# componant_example.net
KiCad netlist of a schematic drawn in Altium Designer
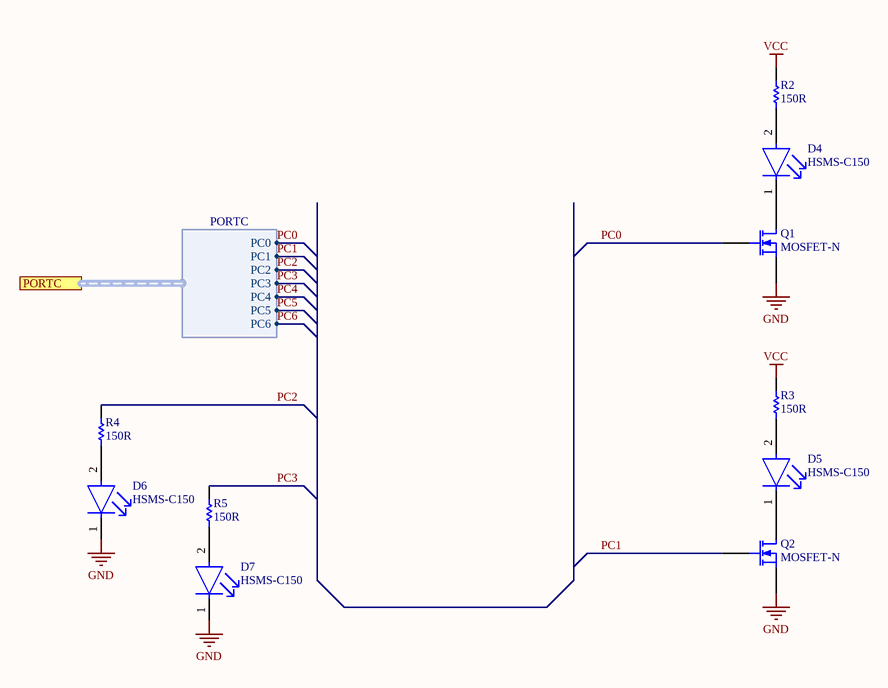
[diagram p0: componant_example.SchDoc]

(export (version "E")
  (design (tool "Eeschema 10.0.6"))
  (components
    (comp (ref "D4")
      (value "HSMS-C150")
      (footprint "FP-HSMS-C150-MFG")
      (description "LED RED DIFFUSED CHIP SMD")
      (libsource (lib "Altium Content Vault") (part "8706943c75ba83719d021d2fdc84c58"))
    )
    (comp (ref "D5")
      (value "HSMS-C150")
      (footprint "FP-HSMS-C150-MFG")
      (description "LED RED DIFFUSED CHIP SMD")
      (libsource (lib "Altium Content Vault") (part "8706943c75ba83719d021d2fdc84c58"))
    )
    (comp (ref "D6")
      (value "HSMS-C150")
      (footprint "FP-HSMS-C150-MFG")
      (description "LED RED DIFFUSED CHIP SMD")
      (libsource (lib "Altium Content Vault") (part "8706943c75ba83719d021d2fdc84c58"))
    )
    (comp (ref "D7")
      (value "HSMS-C150")
      (footprint "FP-HSMS-C150-MFG")
      (description "LED RED DIFFUSED CHIP SMD")
      (libsource (lib "Altium Content Vault") (part "8706943c75ba83719d021d2fdc84c58"))
    )
    (comp (ref "Q1")
      (value "MOSFET-N")
      (description "N-Channel MOSFET\r\n2N7002,215 (SOT23) package")
      (fields (field (name "PUBLISHER") "Altium Limited"))
      (libsource (lib "Other") (part "2N7002"))
    )
    (comp (ref "Q2")
      (value "MOSFET-N")
      (description "N-Channel MOSFET\r\n2N7002,215 (SOT23) package")
      (fields (field (name "PUBLISHER") "Altium Limited"))
      (libsource (lib "Other") (part "2N7002"))
    )
    (comp (ref "R2")
      (value "150R")
      (footprint "RES 0603 SILK")
      (description "Resistor")
      (fields (field (name "PUBLISHER") "Altium Limited"))
      (libsource (lib "Other") (part "150R"))
    )
    (comp (ref "R3")
      (value "150R")
      (footprint "RES 0603 SILK")
      (description "Resistor")
      (fields (field (name "PUBLISHER") "Altium Limited"))
      (libsource (lib "Other") (part "150R"))
    )
    (comp (ref "R4")
      (value "150R")
      (footprint "RES 0603 SILK")
      (description "Resistor")
      (fields (field (name "PUBLISHER") "Altium Limited"))
      (libsource (lib "Other") (part "150R"))
    )
    (comp (ref "R5")
      (value "150R")
      (footprint "RES 0603 SILK")
      (description "Resistor")
      (fields (field (name "PUBLISHER") "Altium Limited"))
      (libsource (lib "Other") (part "150R"))
    )
  )
  (nets
    (net (code "2") (name "/PC0") (class "Default")
      (node (ref "Q1") (pin "2") (pinfunction "G_2") (pintype "passive"))
    )
    (net (code "3") (name "/PC1") (class "Default")
      (node (ref "Q2") (pin "2") (pinfunction "G_2") (pintype "passive"))
    )
    (net (code "4") (name "/PC2") (class "Default")
      (node (ref "R4") (pin "2") (pinfunction "2_2") (pintype "passive"))
    )
    (net (code "5") (name "/PC3") (class "Default")
      (node (ref "R5") (pin "2") (pinfunction "2_2") (pintype "passive"))
    )
    (net (code "10") (name "GND") (class "Default")
      (node (ref "D6") (pin "1") (pinfunction "C_1") (pintype "passive"))
      (node (ref "D7") (pin "1") (pinfunction "C_1") (pintype "passive"))
      (node (ref "Q1") (pin "3") (pinfunction "S_3") (pintype "passive"))
      (node (ref "Q2") (pin "3") (pinfunction "S_3") (pintype "passive"))
    )
    (net (code "11") (name "Net-(D4-A)") (class "Default")
      (node (ref "D4") (pin "2") (pinfunction "A_2") (pintype "passive"))
      (node (ref "R2") (pin "1") (pinfunction "1_1") (pintype "passive"))
    )
    (net (code "12") (name "Net-(D4-C)") (class "Default")
      (node (ref "D4") (pin "1") (pinfunction "C_1") (pintype "passive"))
      (node (ref "Q1") (pin "1") (pinfunction "D_1") (pintype "passive"))
    )
    (net (code "13") (name "Net-(D5-A)") (class "Default")
      (node (ref "D5") (pin "2") (pinfunction "A_2") (pintype "passive"))
      (node (ref "R3") (pin "1") (pinfunction "1_1") (pintype "passive"))
    )
    (net (code "14") (name "Net-(D5-C)") (class "Default")
      (node (ref "D5") (pin "1") (pinfunction "C_1") (pintype "passive"))
      (node (ref "Q2") (pin "1") (pinfunction "D_1") (pintype "passive"))
    )
    (net (code "15") (name "Net-(D6-A)") (class "Default")
      (node (ref "D6") (pin "2") (pinfunction "A_2") (pintype "passive"))
      (node (ref "R4") (pin "1") (pinfunction "1_1") (pintype "passive"))
    )
    (net (code "16") (name "Net-(D7-A)") (class "Default")
      (node (ref "D7") (pin "2") (pinfunction "A_2") (pintype "passive"))
      (node (ref "R5") (pin "1") (pinfunction "1_1") (pintype "passive"))
    )
    (net (code "17") (name "VCC") (class "Default")
      (node (ref "R2") (pin "2") (pinfunction "2_2") (pintype "passive"))
      (node (ref "R3") (pin "2") (pinfunction "2_2") (pintype "passive"))
    )
  )
)
